# bleumaus-oshchip-mk-1_0_0.net
KiCad netlist of a schematic drawn in EAGLE
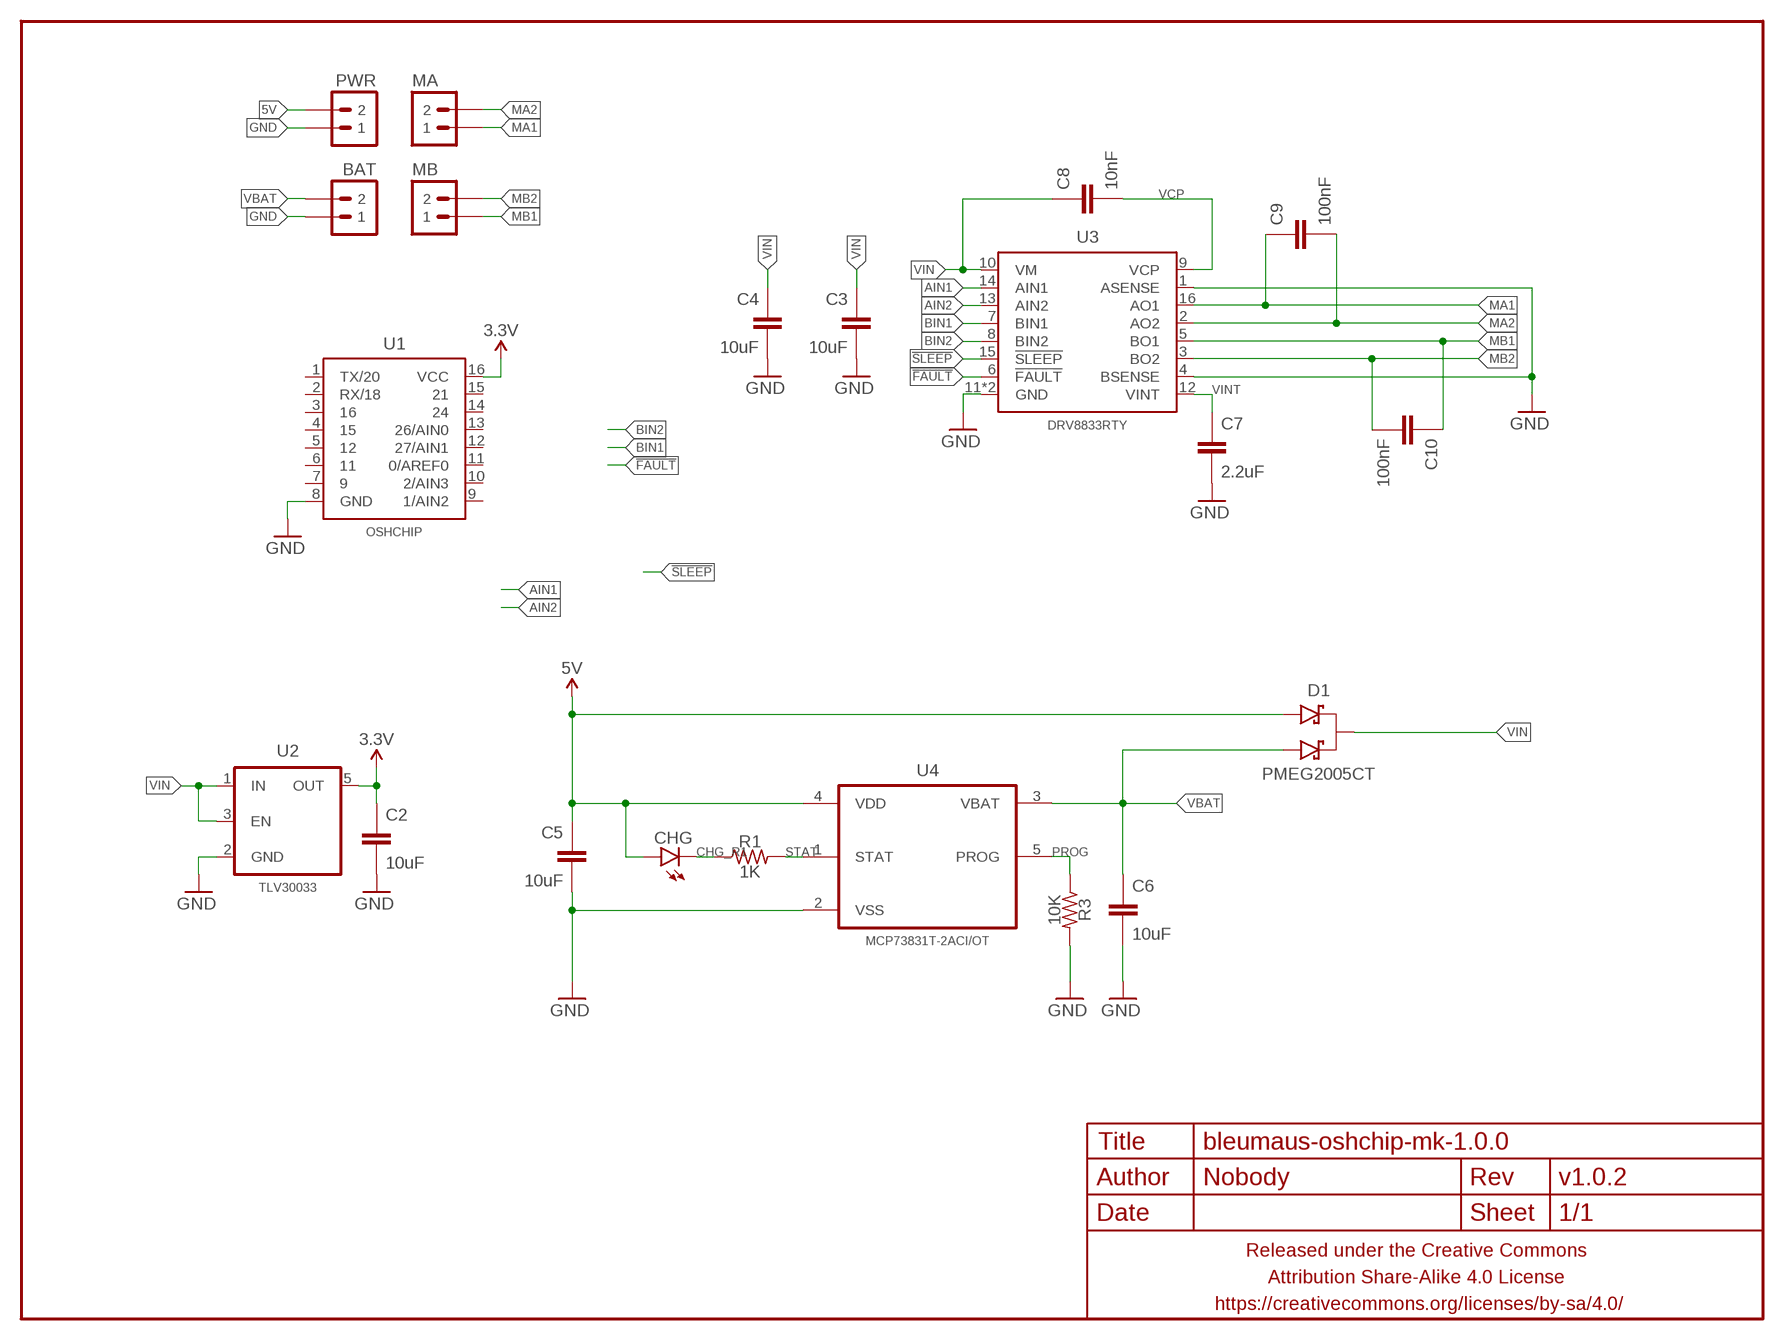
[diagram p0: schematic, sheet 1]

(export (version "E")
  (design (tool "Eeschema 10.0.6"))
  (components
    (comp (ref "BAT")
      (value "M02PTH-2MM")
      (footprint "eagle-import:1X02-2MM-PTH")
      (libsource (lib "eagle-import") (part "M02PTH-2MM"))
    )
    (comp (ref "C2")
      (value "10uF")
      (footprint "eagle-import:C0402")
      (libsource (lib "eagle-import") (part "CAPACITOR-CERAMICC0402"))
    )
    (comp (ref "C3")
      (value "10uF")
      (footprint "eagle-import:C1206")
      (libsource (lib "eagle-import") (part "CAPACITOR-CERAMICC1206"))
    )
    (comp (ref "C4")
      (value "10uF")
      (footprint "eagle-import:C1206")
      (libsource (lib "eagle-import") (part "CAPACITOR-CERAMICC1206"))
    )
    (comp (ref "C5")
      (value "10uF")
      (footprint "eagle-import:C0402")
      (libsource (lib "eagle-import") (part "CAPACITOR-CERAMICC0402"))
    )
    (comp (ref "C6")
      (value "10uF")
      (footprint "eagle-import:C0402")
      (libsource (lib "eagle-import") (part "CAPACITOR-CERAMICC0402"))
    )
    (comp (ref "C7")
      (value "2.2uF")
      (footprint "eagle-import:C0402")
      (libsource (lib "eagle-import") (part "CAPACITOR-CERAMICC0402"))
    )
    (comp (ref "C8")
      (value "10nF")
      (footprint "eagle-import:C0402")
      (libsource (lib "eagle-import") (part "CAPACITOR-CERAMICC0402"))
    )
    (comp (ref "C9")
      (value "100nF")
      (footprint "eagle-import:C0402")
      (libsource (lib "eagle-import") (part "CAPACITOR-CERAMICC0402"))
    )
    (comp (ref "C10")
      (value "100nF")
      (footprint "eagle-import:C0402")
      (libsource (lib "eagle-import") (part "CAPACITOR-CERAMICC0402"))
    )
    (comp (ref "CHG")
      (value "LED0603-TIGHT")
      (footprint "eagle-import:LED-0603-TIGHT")
      (libsource (lib "eagle-import") (part "LED0603-TIGHT"))
    )
    (comp (ref "D1")
      (value "PMEG2005CT")
      (footprint "eagle-import:SOT23")
      (libsource (lib "eagle-import") (part "DIODE-SCHOTTKY-DUALPMEG2005CT"))
    )
    (comp (ref "FRAME1")
      (value "FRAME-LETTERNO_PACKAGE")
      (footprint "eagle-import:DUMMY")
      (fields
        (field (name "DESIGNER") "Nobody")
        (field (name "VERSION") "v1.0.2")
        (field (name "VERSION_1") "v1.0.2")
      )
      (libsource (lib "eagle-import") (part "FRAME-LETTERNO_PACKAGE"))
    )
    (comp (ref "MA")
      (value "M02PTH-2MM")
      (footprint "eagle-import:1X02-2MM-PTH")
      (libsource (lib "eagle-import") (part "M02PTH-2MM"))
    )
    (comp (ref "MB")
      (value "M02PTH-2MM")
      (footprint "eagle-import:1X02-2MM-PTH")
      (libsource (lib "eagle-import") (part "M02PTH-2MM"))
    )
    (comp (ref "PWR")
      (value "M02PTH-2MM")
      (footprint "eagle-import:1X02-2MM-PTH")
      (libsource (lib "eagle-import") (part "M02PTH-2MM"))
    )
    (comp (ref "R1")
      (value "1K")
      (footprint "eagle-import:R0402")
      (libsource (lib "eagle-import") (part "RESISTORR0402"))
    )
    (comp (ref "R3")
      (value "10K")
      (footprint "eagle-import:R0402")
      (libsource (lib "eagle-import") (part "RESISTORR0402"))
    )
    (comp (ref "U1")
      (value "OSHCHIP")
      (footprint "eagle-import:DIL16")
      (libsource (lib "eagle-import") (part "OSHCHIP"))
    )
    (comp (ref "U2")
      (value "TLV30033")
      (footprint "eagle-import:SC70-TIGHTER")
      (libsource (lib "eagle-import") (part "V_REG_ENTLV700XXDCK-TIGHTER"))
    )
    (comp (ref "U3")
      (value "DRV8833RTY")
      (footprint "eagle-import:PWQFN-16")
      (libsource (lib "eagle-import") (part "DRV8833RTY"))
    )
    (comp (ref "U4")
      (value "MCP73831T-2ACI/OT")
      (footprint "eagle-import:SOT95P280X145-5N")
      (libsource (lib "eagle-import") (part "MCP73831T-2ACI/OT"))
    )
  )
  (nets
    (net (code "1") (name "/CHG_R1") (class "Default")
      (node (ref "CHG") (pin "C") (pinfunction "C_C") (pintype "passive"))
      (node (ref "R1") (pin "1") (pinfunction "1_1") (pintype "passive"))
    )
    (net (code "2") (name "/PROG") (class "Default")
      (node (ref "R3") (pin "1") (pinfunction "1_1") (pintype "passive"))
      (node (ref "U4") (pin "5") (pinfunction "PROG_5") (pintype "input"))
    )
    (net (code "3") (name "/STAT") (class "Default")
      (node (ref "R1") (pin "2") (pinfunction "2_2") (pintype "passive"))
      (node (ref "U4") (pin "1") (pinfunction "STAT_1") (pintype "output"))
    )
    (net (code "4") (name "/VCP") (class "Default")
      (node (ref "C8") (pin "2") (pinfunction "2_2") (pintype "passive"))
      (node (ref "U3") (pin "9") (pinfunction "VCP_9") (pintype "bidirectional"))
    )
    (net (code "5") (name "/VINT") (class "Default")
      (node (ref "C7") (pin "1") (pinfunction "1_1") (pintype "passive"))
      (node (ref "U3") (pin "12") (pinfunction "VINT_12") (pintype "bidirectional"))
    )
    (net (code "6") (name "/~{FAULT}") (class "Default")
      (node (ref "U3") (pin "6") (pinfunction "~{FAULT}_6") (pintype "output"))
    )
    (net (code "7") (name "/~{SLEEP}") (class "Default")
      (node (ref "U3") (pin "15") (pinfunction "~{SLEEP}_15") (pintype "input"))
    )
    (net (code "8") (name "3.3V") (class "Default")
      (node (ref "C2") (pin "1") (pinfunction "1_1") (pintype "passive"))
      (node (ref "U1") (pin "16") (pinfunction "VCC_16") (pintype "bidirectional"))
      (node (ref "U2") (pin "5") (pinfunction "OUT_5") (pintype "passive"))
    )
    (net (code "9") (name "5V") (class "Default")
      (node (ref "C5") (pin "1") (pinfunction "1_1") (pintype "passive"))
      (node (ref "CHG") (pin "A") (pinfunction "A_A") (pintype "passive"))
      (node (ref "D1") (pin "1") (pinfunction "A1_1") (pintype "passive"))
      (node (ref "PWR") (pin "P$2") (pinfunction "2_P$2") (pintype "passive"))
      (node (ref "U4") (pin "4") (pinfunction "VDD_4") (pintype "power_in"))
    )
    (net (code "10") (name "AIN1") (class "Default")
      (node (ref "U3") (pin "14") (pinfunction "AIN1_14") (pintype "input"))
    )
    (net (code "11") (name "AIN2") (class "Default")
      (node (ref "U3") (pin "13") (pinfunction "AIN2_13") (pintype "input"))
    )
    (net (code "12") (name "BIN1") (class "Default")
      (node (ref "U3") (pin "7") (pinfunction "BIN1_7") (pintype "input"))
    )
    (net (code "13") (name "BIN2") (class "Default")
      (node (ref "U3") (pin "8") (pinfunction "BIN2_8") (pintype "input"))
    )
    (net (code "14") (name "GND") (class "Default")
      (node (ref "BAT") (pin "P$1") (pinfunction "1_P$1") (pintype "passive"))
      (node (ref "C2") (pin "2") (pinfunction "2_2") (pintype "passive"))
      (node (ref "C3") (pin "2") (pinfunction "2_2") (pintype "passive"))
      (node (ref "C4") (pin "2") (pinfunction "2_2") (pintype "passive"))
      (node (ref "C5") (pin "2") (pinfunction "2_2") (pintype "passive"))
      (node (ref "C6") (pin "2") (pinfunction "2_2") (pintype "passive"))
      (node (ref "C7") (pin "2") (pinfunction "2_2") (pintype "passive"))
      (node (ref "PWR") (pin "P$1") (pinfunction "1_P$1") (pintype "passive"))
      (node (ref "R3") (pin "2") (pinfunction "2_2") (pintype "passive"))
      (node (ref "U1") (pin "8") (pinfunction "GND_8") (pintype "bidirectional"))
      (node (ref "U2") (pin "2") (pinfunction "GND_2") (pintype "input"))
      (node (ref "U3") (pin "1") (pinfunction "ASENSE_1") (pintype "bidirectional"))
      (node (ref "U3") (pin "11") (pinfunction "GND_11") (pintype "bidirectional"))
      (node (ref "U3") (pin "17") (pinfunction "GND_17") (pintype "bidirectional"))
      (node (ref "U3") (pin "4") (pinfunction "BSENSE_4") (pintype "bidirectional"))
      (node (ref "U4") (pin "2") (pinfunction "VSS_2") (pintype "power_in"))
    )
    (net (code "15") (name "MA1") (class "Default")
      (node (ref "C9") (pin "1") (pinfunction "1_1") (pintype "passive"))
      (node (ref "MA") (pin "P$1") (pinfunction "1_P$1") (pintype "passive"))
      (node (ref "U3") (pin "16") (pinfunction "AO1_16") (pintype "bidirectional"))
    )
    (net (code "16") (name "MA2") (class "Default")
      (node (ref "C9") (pin "2") (pinfunction "2_2") (pintype "passive"))
      (node (ref "MA") (pin "P$2") (pinfunction "2_P$2") (pintype "passive"))
      (node (ref "U3") (pin "2") (pinfunction "AO2_2") (pintype "bidirectional"))
    )
    (net (code "17") (name "MB1") (class "Default")
      (node (ref "C10") (pin "1") (pinfunction "1_1") (pintype "passive"))
      (node (ref "MB") (pin "P$1") (pinfunction "1_P$1") (pintype "passive"))
      (node (ref "U3") (pin "5") (pinfunction "BO1_5") (pintype "bidirectional"))
    )
    (net (code "18") (name "MB2") (class "Default")
      (node (ref "C10") (pin "2") (pinfunction "2_2") (pintype "passive"))
      (node (ref "MB") (pin "P$2") (pinfunction "2_P$2") (pintype "passive"))
      (node (ref "U3") (pin "3") (pinfunction "BO2_3") (pintype "bidirectional"))
    )
    (net (code "19") (name "VBAT") (class "Default")
      (node (ref "BAT") (pin "P$2") (pinfunction "2_P$2") (pintype "passive"))
      (node (ref "C6") (pin "1") (pinfunction "1_1") (pintype "passive"))
      (node (ref "D1") (pin "2") (pinfunction "A2_2") (pintype "passive"))
      (node (ref "U4") (pin "3") (pinfunction "VBAT_3") (pintype "output"))
    )
    (net (code "20") (name "VIN") (class "Default")
      (node (ref "C3") (pin "1") (pinfunction "1_1") (pintype "passive"))
      (node (ref "C4") (pin "1") (pinfunction "1_1") (pintype "passive"))
      (node (ref "C8") (pin "1") (pinfunction "1_1") (pintype "passive"))
      (node (ref "D1") (pin "3") (pinfunction "K_3") (pintype "passive"))
      (node (ref "U2") (pin "1") (pinfunction "IN_1") (pintype "input"))
      (node (ref "U2") (pin "3") (pinfunction "EN_3") (pintype "input"))
      (node (ref "U3") (pin "10") (pinfunction "VM_10") (pintype "bidirectional"))
    )
    (net (code "21") (name "unconnected-(U1-0{slash}AREF0-Pad11)") (class "Default")
      (node (ref "U1") (pin "11") (pinfunction "0/AREF0_11") (pintype "bidirectional"))
    )
    (net (code "22") (name "unconnected-(U1-1{slash}AIN2-Pad9)") (class "Default")
      (node (ref "U1") (pin "9") (pinfunction "1/AIN2_9") (pintype "bidirectional"))
    )
    (net (code "23") (name "unconnected-(U1-2{slash}AIN3-Pad10)") (class "Default")
      (node (ref "U1") (pin "10") (pinfunction "2/AIN3_10") (pintype "bidirectional"))
    )
    (net (code "24") (name "unconnected-(U1-9-Pad7)") (class "Default")
      (node (ref "U1") (pin "7") (pinfunction "9_7") (pintype "bidirectional"))
    )
    (net (code "25") (name "unconnected-(U1-11-Pad6)") (class "Default")
      (node (ref "U1") (pin "6") (pinfunction "11_6") (pintype "bidirectional"))
    )
    (net (code "26") (name "unconnected-(U1-12-Pad5)") (class "Default")
      (node (ref "U1") (pin "5") (pinfunction "12_5") (pintype "bidirectional"))
    )
    (net (code "27") (name "unconnected-(U1-15-Pad4)") (class "Default")
      (node (ref "U1") (pin "4") (pinfunction "15_4") (pintype "bidirectional"))
    )
    (net (code "28") (name "unconnected-(U1-16-Pad3)") (class "Default")
      (node (ref "U1") (pin "3") (pinfunction "16_3") (pintype "bidirectional"))
    )
    (net (code "29") (name "unconnected-(U1-21-Pad15)") (class "Default")
      (node (ref "U1") (pin "15") (pinfunction "21_15") (pintype "bidirectional"))
    )
    (net (code "30") (name "unconnected-(U1-24-Pad14)") (class "Default")
      (node (ref "U1") (pin "14") (pinfunction "24_14") (pintype "bidirectional"))
    )
    (net (code "31") (name "unconnected-(U1-26{slash}AIN0-Pad13)") (class "Default")
      (node (ref "U1") (pin "13") (pinfunction "26/AIN0_13") (pintype "bidirectional"))
    )
    (net (code "32") (name "unconnected-(U1-27{slash}AIN1-Pad12)") (class "Default")
      (node (ref "U1") (pin "12") (pinfunction "27/AIN1_12") (pintype "bidirectional"))
    )
    (net (code "33") (name "unconnected-(U1-RX{slash}18-Pad2)") (class "Default")
      (node (ref "U1") (pin "2") (pinfunction "RX/18_2") (pintype "bidirectional"))
    )
    (net (code "34") (name "unconnected-(U1-TX{slash}20-Pad1)") (class "Default")
      (node (ref "U1") (pin "1") (pinfunction "TX/20_1") (pintype "bidirectional"))
    )
  )
)
